# Vest.net
KiCad netlist of a schematic drawn in Altium Designer
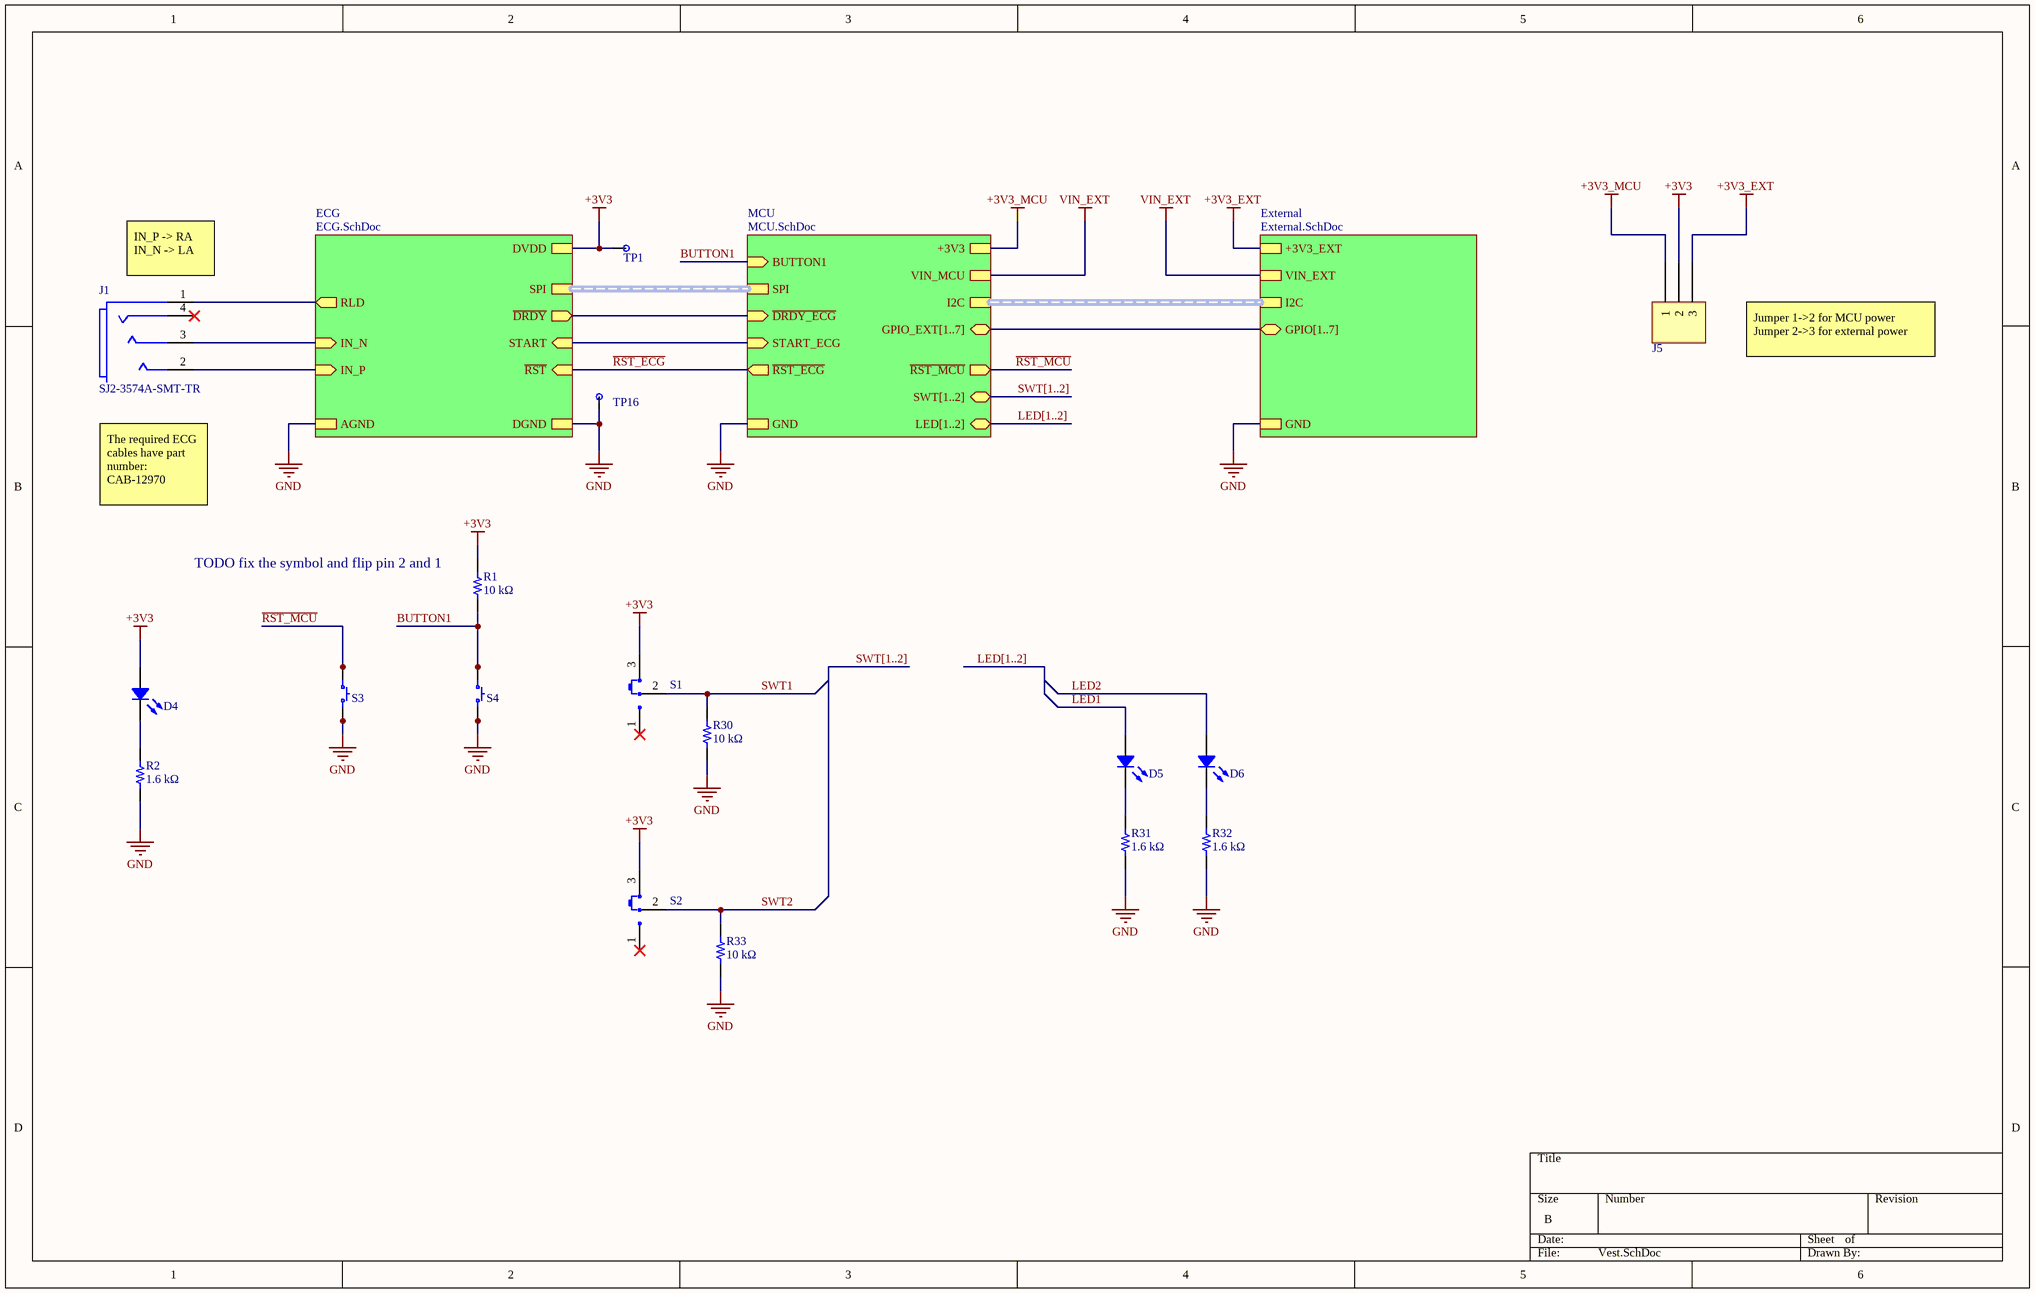
[diagram p0: Vest.SchDoc]

(export (version "E")
  (design (tool "Eeschema 10.0.6"))
  (components
    (comp (ref "D4")
      (value "Red")
      (footprint "LED 1206_3216 RED")
      (description "LED RED CLEAR 2SMD")
      (fields (field (name "PART NUMBER") "APT3216LSECK/J3-PRV") (field (name "MANUFACTURER") "Kingbright"))
      (libsource (lib "Generic Altium Database") (part "LED"))
    )
    (comp (ref "D5")
      (value "Red")
      (footprint "LED 1206_3216 RED")
      (description "LED RED CLEAR 2SMD")
      (fields (field (name "PART NUMBER") "APT3216LSECK/J3-PRV") (field (name "MANUFACTURER") "Kingbright"))
      (libsource (lib "Generic Altium Database") (part "LED"))
    )
    (comp (ref "D6")
      (value "Red")
      (footprint "LED 1206_3216 RED")
      (description "LED RED CLEAR 2SMD")
      (fields (field (name "PART NUMBER") "APT3216LSECK/J3-PRV") (field (name "MANUFACTURER") "Kingbright"))
      (libsource (lib "Generic Altium Database") (part "LED"))
    )
    (comp (ref "J1")
      (value "SJ2-3574A-SMT-TR")
      (footprint "CUI SJ2-3574A-SMT-TR")
      (description "AUDIO JACK, 3.5 MM, RT, 4 CONDUC")
      (fields (field (name "MANUFACTURER") "CUI Devices"))
      (libsource (lib "Generic Altium Database") (part "CUI SJ2-3574A-SMT-TR"))
    )
    (comp (ref "J5")
      (value "0022272031")
      (footprint "MOLEX KK 0022272031")
      (description "CONN HEADER VERT 3POS 2.54MM")
      (fields (field (name "MANUFACTURER") "Molex"))
      (libsource (lib "Generic Altium Database") (part "3 Pin"))
    )
    (comp (ref "R1")
      (value "10 kΩ")
      (footprint "RES 0402_1005")
      (description "RES SMD 10K OHM 1% 1/16W 0402")
      (fields (field (name "PART NUMBER") "AC0402FR-0710KL") (field (name "MANUFACTURER") "Yageo"))
      (libsource (lib "Generic Altium Database") (part "Resistor"))
    )
    (comp (ref "R2")
      (value "1.6 kΩ")
      (footprint "RES 0402_1005")
      (description "RES SMD 1.6K OHM 1% 1/16W 0402")
      (fields (field (name "PART NUMBER") "CRCW04021K60FKED") (field (name "MANUFACTURER") "Vishay Dale"))
      (libsource (lib "Generic Altium Database") (part "Resistor"))
    )
    (comp (ref "R30")
      (value "10 kΩ")
      (footprint "RES 0402_1005")
      (description "RES SMD 10K OHM 1% 1/16W 0402")
      (fields (field (name "PART NUMBER") "AC0402FR-0710KL") (field (name "MANUFACTURER") "Yageo"))
      (libsource (lib "Generic Altium Database") (part "Resistor"))
    )
    (comp (ref "R31")
      (value "1.6 kΩ")
      (footprint "RES 0402_1005")
      (description "RES SMD 1.6K OHM 1% 1/16W 0402")
      (fields (field (name "PART NUMBER") "CRCW04021K60FKED") (field (name "MANUFACTURER") "Vishay Dale"))
      (libsource (lib "Generic Altium Database") (part "Resistor"))
    )
    (comp (ref "R32")
      (value "1.6 kΩ")
      (footprint "RES 0402_1005")
      (description "RES SMD 1.6K OHM 1% 1/16W 0402")
      (fields (field (name "PART NUMBER") "CRCW04021K60FKED") (field (name "MANUFACTURER") "Vishay Dale"))
      (libsource (lib "Generic Altium Database") (part "Resistor"))
    )
    (comp (ref "R33")
      (value "10 kΩ")
      (footprint "RES 0402_1005")
      (description "RES SMD 10K OHM 1% 1/16W 0402")
      (fields (field (name "PART NUMBER") "AC0402FR-0710KL") (field (name "MANUFACTURER") "Yageo"))
      (libsource (lib "Generic Altium Database") (part "Resistor"))
    )
    (comp (ref "S1")
      (value "CUS-12TB")
      (footprint "NCE CUS-12TB")
      (description "SWITCH SLIDE SPDT 300MA 4V")
      (fields (field (name "MANUFACTURER") "Nidec Copal Electronics"))
      (libsource (lib "Generic Altium Database") (part "NCE CUS-12TB"))
    )
    (comp (ref "S2")
      (value "CUS-12TB")
      (footprint "NCE CUS-12TB")
      (description "SWITCH SLIDE SPDT 300MA 4V")
      (fields (field (name "MANUFACTURER") "Nidec Copal Electronics"))
      (libsource (lib "Generic Altium Database") (part "NCE CUS-12TB"))
    )
    (comp (ref "S3")
      (value "1571563-4")
      (footprint "TE FSM4JSMA")
      (description "SWITCH TACTILE SPST-NO 0.05A 24V")
      (fields (field (name "MANUFACTURER") "TE Connectivity ALCOSWITCH Switches"))
      (libsource (lib "Generic Altium Database") (part "SPST-NO 4 PIN"))
    )
    (comp (ref "S4")
      (value "1571563-4")
      (footprint "TE FSM4JSMA")
      (description "SWITCH TACTILE SPST-NO 0.05A 24V")
      (fields (field (name "MANUFACTURER") "TE Connectivity ALCOSWITCH Switches"))
      (libsource (lib "Generic Altium Database") (part "SPST-NO 4 PIN"))
    )
    (comp (ref "TP1")
      (value "TP2MM")
      (footprint "Test Point 2MM")
      (description "2MM Circular Test Point")
      (libsource (lib "Generic Altium Database") (part "Test Point"))
    )
    (comp (ref "TP16")
      (value "TP2MM")
      (footprint "Test Point 2MM")
      (description "2MM Circular Test Point")
      (libsource (lib "Generic Altium Database") (part "Test Point"))
    )
  )
  (nets
    (net (code "1") (name "+3V3") (class "Default")
      (node (ref "D4") (pin "1") (pinfunction "1_1") (pintype "passive"))
      (node (ref "J5") (pin "2") (pinfunction "2_2") (pintype "passive"))
      (node (ref "R1") (pin "1") (pinfunction "1_1") (pintype "passive"))
      (node (ref "S1") (pin "3") (pinfunction "3_3") (pintype "passive"))
      (node (ref "S2") (pin "3") (pinfunction "3_3") (pintype "passive"))
      (node (ref "TP1") (pin "1") (pintype "power_in"))
    )
    (net (code "2") (name "+3V3_EXT") (class "Default")
      (node (ref "J5") (pin "3") (pinfunction "3_3") (pintype "passive"))
    )
    (net (code "3") (name "+3V3_MCU") (class "Default")
      (node (ref "J5") (pin "1") (pinfunction "1_1") (pintype "passive"))
    )
    (net (code "4") (name "/BUTTON1") (class "Default")
      (node (ref "R1") (pin "2") (pinfunction "2_2") (pintype "passive"))
      (node (ref "S4") (pin "1") (pinfunction "1_1") (pintype "passive"))
      (node (ref "S4") (pin "2") (pinfunction "2_2") (pintype "passive"))
    )
    (net (code "7") (name "/IN_N") (class "Default")
      (node (ref "J1") (pin "3") (pinfunction "ring_1_3") (pintype "passive"))
    )
    (net (code "8") (name "/IN_P") (class "Default")
      (node (ref "J1") (pin "2") (pinfunction "tip_2") (pintype "passive"))
    )
    (net (code "9") (name "/LED1") (class "Default")
      (node (ref "D5") (pin "1") (pinfunction "1_1") (pintype "passive"))
    )
    (net (code "10") (name "/LED2") (class "Default")
      (node (ref "D6") (pin "1") (pinfunction "1_1") (pintype "passive"))
    )
    (net (code "12") (name "/RLD") (class "Default")
      (node (ref "J1") (pin "1") (pinfunction "sleeve_1") (pintype "passive"))
    )
    (net (code "15") (name "/SWT1") (class "Default")
      (node (ref "R30") (pin "1") (pinfunction "1_1") (pintype "passive"))
      (node (ref "S1") (pin "2") (pinfunction "COM_2") (pintype "passive"))
    )
    (net (code "16") (name "/SWT2") (class "Default")
      (node (ref "R33") (pin "1") (pinfunction "1_1") (pintype "passive"))
      (node (ref "S2") (pin "2") (pinfunction "COM_2") (pintype "passive"))
    )
    (net (code "20") (name "/~{RST_MCU}") (class "Default")
      (node (ref "S3") (pin "1") (pinfunction "1_1") (pintype "passive"))
      (node (ref "S3") (pin "2") (pinfunction "2_2") (pintype "passive"))
    )
    (net (code "21") (name "GND") (class "Default")
      (node (ref "R2") (pin "1") (pinfunction "1_1") (pintype "passive"))
      (node (ref "R30") (pin "2") (pinfunction "2_2") (pintype "passive"))
      (node (ref "R31") (pin "1") (pinfunction "1_1") (pintype "passive"))
      (node (ref "R32") (pin "1") (pinfunction "1_1") (pintype "passive"))
      (node (ref "R33") (pin "2") (pinfunction "2_2") (pintype "passive"))
      (node (ref "S3") (pin "3") (pinfunction "3_3") (pintype "passive"))
      (node (ref "S3") (pin "4") (pinfunction "4_4") (pintype "passive"))
      (node (ref "S4") (pin "3") (pinfunction "3_3") (pintype "passive"))
      (node (ref "S4") (pin "4") (pinfunction "4_4") (pintype "passive"))
      (node (ref "TP16") (pin "1") (pintype "power_in"))
    )
    (net (code "22") (name "Net-(D4-Pad2)") (class "Default")
      (node (ref "D4") (pin "2") (pinfunction "2_2") (pintype "passive"))
      (node (ref "R2") (pin "2") (pinfunction "2_2") (pintype "passive"))
    )
    (net (code "23") (name "Net-(D5-Pad2)") (class "Default")
      (node (ref "D5") (pin "2") (pinfunction "2_2") (pintype "passive"))
      (node (ref "R31") (pin "2") (pinfunction "2_2") (pintype "passive"))
    )
    (net (code "24") (name "Net-(D6-Pad2)") (class "Default")
      (node (ref "D6") (pin "2") (pinfunction "2_2") (pintype "passive"))
      (node (ref "R32") (pin "2") (pinfunction "2_2") (pintype "passive"))
    )
    (net (code "26") (name "unconnected-(J1-ring_2-Pad4)") (class "Default")
      (node (ref "J1") (pin "4") (pinfunction "ring_2_4") (pintype "passive+no_connect"))
    )
    (net (code "27") (name "unconnected-(S1-Pad1)") (class "Default")
      (node (ref "S1") (pin "1") (pinfunction "1_1") (pintype "passive+no_connect"))
    )
    (net (code "28") (name "unconnected-(S2-Pad1)") (class "Default")
      (node (ref "S2") (pin "1") (pinfunction "1_1") (pintype "passive+no_connect"))
    )
  )
)
